# M206X.net
KiCad netlist of a schematic drawn in EAGLE
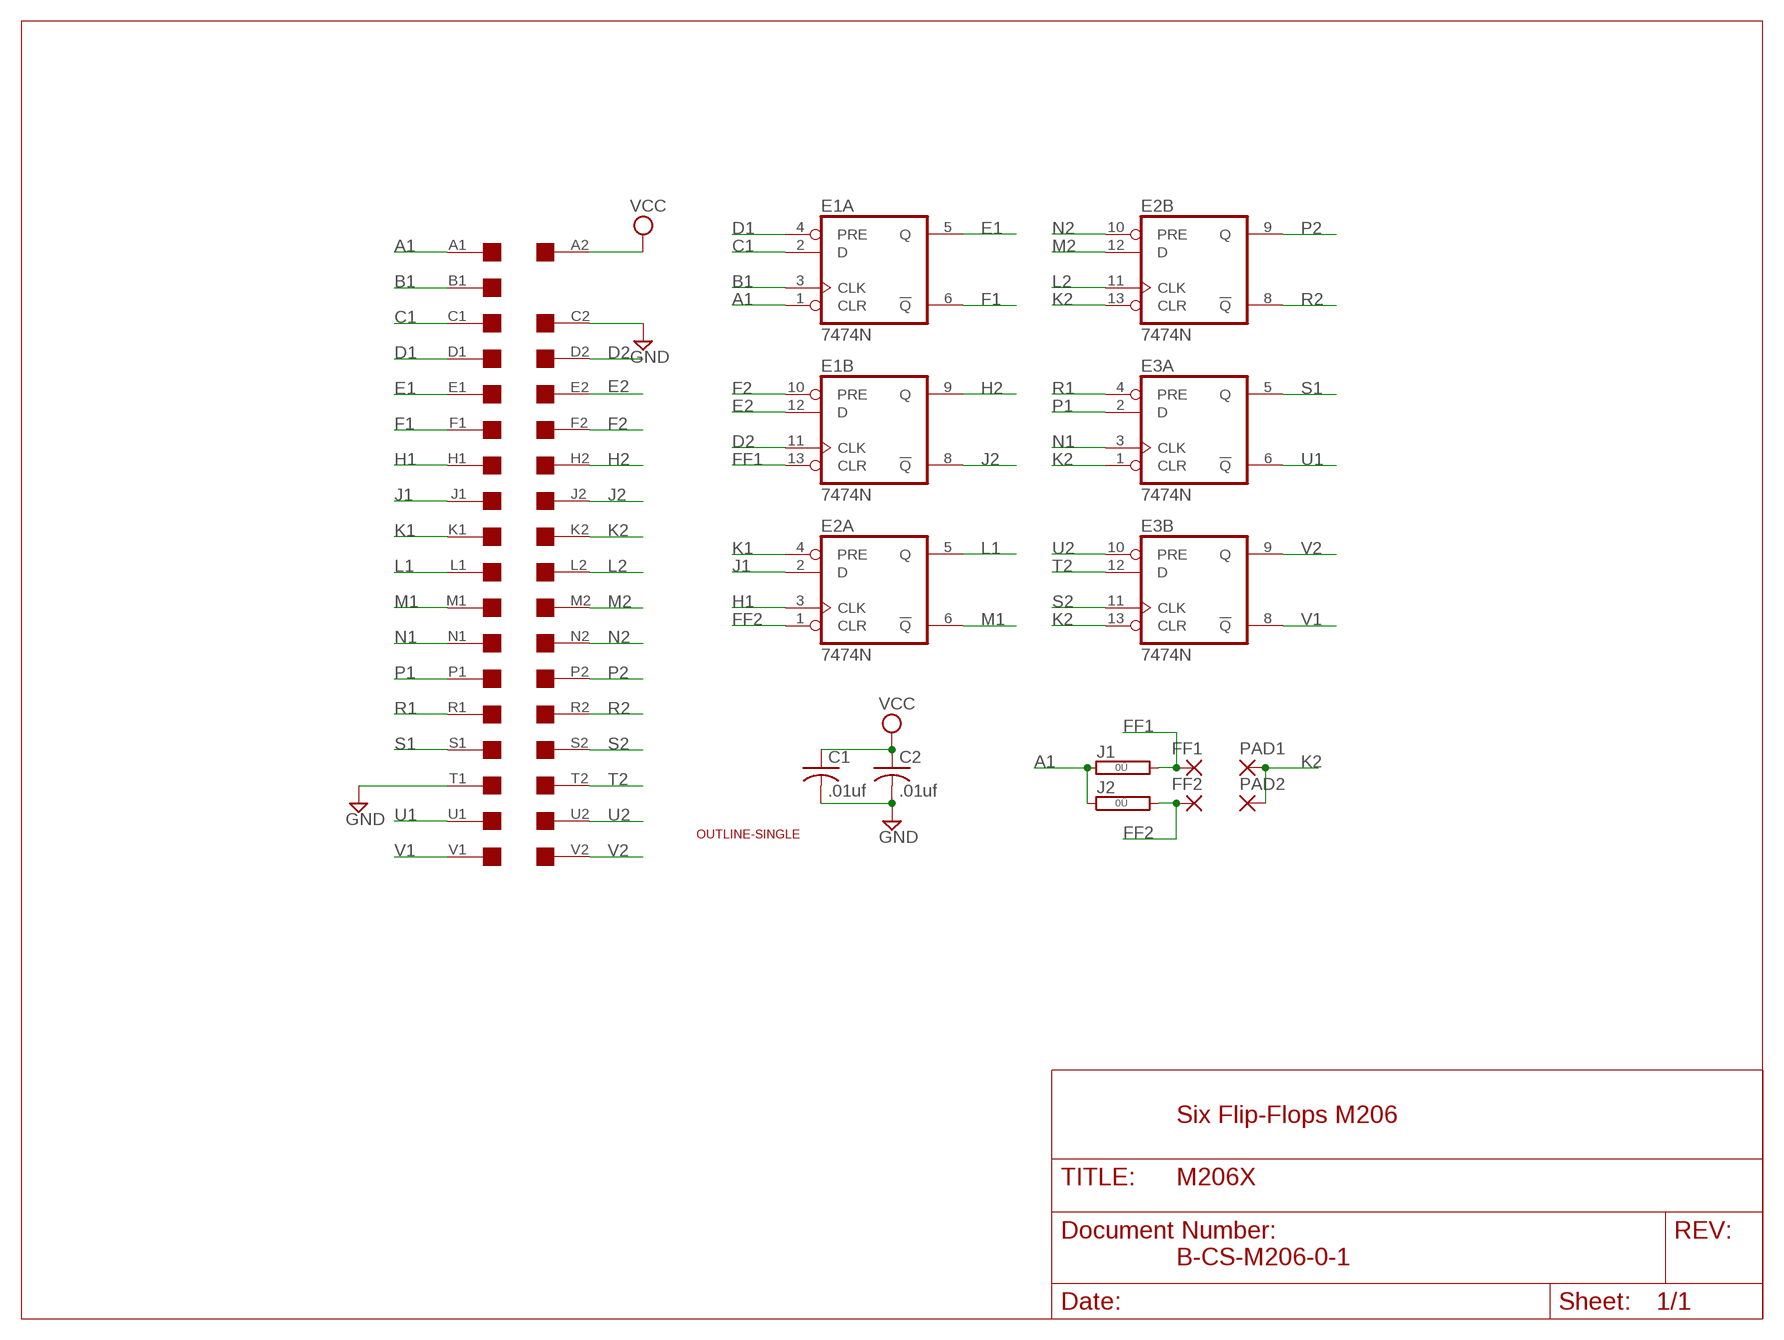
[diagram p0: schematic, sheet 1]

(export (version "E")
  (design (tool "Eeschema 10.0.6"))
  (components
    (comp (ref "C1")
      (value ".01uf")
      (footprint "eagle-import:C050-025X075")
      (libsource (lib "eagle-import") (part "C-US050-025X075"))
    )
    (comp (ref "C2")
      (value ".01uf")
      (footprint "eagle-import:C050-025X075")
      (libsource (lib "eagle-import") (part "C-US050-025X075"))
    )
    (comp (ref "E1")
      (value "7474N")
      (footprint "eagle-import:DIL14")
      (libsource (lib "eagle-import") (part "7474NS"))
    )
    (comp (ref "E2")
      (value "7474N")
      (footprint "eagle-import:DIL14")
      (libsource (lib "eagle-import") (part "7474NS"))
    )
    (comp (ref "E3")
      (value "7474N")
      (footprint "eagle-import:DIL14")
      (libsource (lib "eagle-import") (part "7474NS"))
    )
    (comp (ref "FF1")
      (value "1,6/0,8")
      (footprint "eagle-import:1,6_0,8")
      (libsource (lib "eagle-import") (part "1,6/0,8"))
    )
    (comp (ref "FF2")
      (value "1,6/0,8")
      (footprint "eagle-import:1,6_0,8")
      (libsource (lib "eagle-import") (part "1,6/0,8"))
    )
    (comp (ref "J1")
      (value "0R")
      (footprint "eagle-import:0R_10")
      (libsource (lib "eagle-import") (part "0R"))
    )
    (comp (ref "J2")
      (value "0R")
      (footprint "eagle-import:0R_10")
      (libsource (lib "eagle-import") (part "0R"))
    )
    (comp (ref "PAD1")
      (value "1,6/0,8")
      (footprint "eagle-import:1,6_0,8")
      (libsource (lib "eagle-import") (part "1,6/0,8"))
    )
    (comp (ref "PAD2")
      (value "1,6/0,8")
      (footprint "eagle-import:1,6_0,8")
      (libsource (lib "eagle-import") (part "1,6/0,8"))
    )
    (comp (ref "U$1")
      (value "OUTLINE-SINGLE")
      (footprint "eagle-import:SINGLE")
      (libsource (lib "eagle-import") (part "OUTLINE-SINGLE"))
    )
    (comp (ref "U$4")
      (value "SINGLE")
      (footprint "eagle-import:EDGE-CON2")
      (libsource (lib "eagle-import") (part "SINGLE"))
    )
  )
  (nets
    (net (code "1") (name "/A1") (class "Default")
      (node (ref "E1") (pin "1") (pinfunction "CLR_1") (pintype "input"))
      (node (ref "J1") (pin "1") (pinfunction "1_1") (pintype "passive"))
      (node (ref "J2") (pin "1") (pinfunction "1_1") (pintype "passive"))
      (node (ref "U$4") (pin "A1") (pinfunction "1_A1") (pintype "bidirectional"))
    )
    (net (code "2") (name "/B1") (class "Default")
      (node (ref "E1") (pin "3") (pinfunction "CLK_3") (pintype "input"))
      (node (ref "U$4") (pin "B1") (pinfunction "1_B1") (pintype "bidirectional"))
    )
    (net (code "3") (name "/C1") (class "Default")
      (node (ref "E1") (pin "2") (pinfunction "D_2") (pintype "input"))
      (node (ref "U$4") (pin "C1") (pinfunction "1_C1") (pintype "bidirectional"))
    )
    (net (code "4") (name "/D1") (class "Default")
      (node (ref "E1") (pin "4") (pinfunction "PRE_4") (pintype "input"))
      (node (ref "U$4") (pin "D1") (pinfunction "1_D1") (pintype "bidirectional"))
    )
    (net (code "5") (name "/D2") (class "Default")
      (node (ref "E1") (pin "11") (pinfunction "CLK_11") (pintype "input"))
      (node (ref "U$4") (pin "D2") (pinfunction "1_D2") (pintype "bidirectional"))
    )
    (net (code "6") (name "/E1") (class "Default")
      (node (ref "E1") (pin "5") (pinfunction "Q_5") (pintype "output"))
      (node (ref "U$4") (pin "E1") (pinfunction "1_E1") (pintype "bidirectional"))
    )
    (net (code "7") (name "/E2") (class "Default")
      (node (ref "E1") (pin "12") (pinfunction "D_12") (pintype "input"))
      (node (ref "U$4") (pin "E2") (pinfunction "1_E2") (pintype "bidirectional"))
    )
    (net (code "8") (name "/F1") (class "Default")
      (node (ref "E1") (pin "6") (pinfunction "~{Q}_6") (pintype "output"))
      (node (ref "U$4") (pin "F1") (pinfunction "1_F1") (pintype "bidirectional"))
    )
    (net (code "9") (name "/F2") (class "Default")
      (node (ref "E1") (pin "10") (pinfunction "PRE_10") (pintype "input"))
      (node (ref "U$4") (pin "F2") (pinfunction "1_F2") (pintype "bidirectional"))
    )
    (net (code "10") (name "/FF1") (class "Default")
      (node (ref "E1") (pin "13") (pinfunction "CLR_13") (pintype "input"))
      (node (ref "FF1") (pin "1") (pinfunction "P_1") (pintype "passive"))
      (node (ref "J1") (pin "2") (pinfunction "2_2") (pintype "passive"))
    )
    (net (code "11") (name "/FF2") (class "Default")
      (node (ref "E2") (pin "1") (pinfunction "CLR_1") (pintype "input"))
      (node (ref "FF2") (pin "1") (pinfunction "P_1") (pintype "passive"))
      (node (ref "J2") (pin "2") (pinfunction "2_2") (pintype "passive"))
    )
    (net (code "12") (name "/H1") (class "Default")
      (node (ref "E2") (pin "3") (pinfunction "CLK_3") (pintype "input"))
      (node (ref "U$4") (pin "H1") (pinfunction "1_H1") (pintype "bidirectional"))
    )
    (net (code "13") (name "/H2") (class "Default")
      (node (ref "E1") (pin "9") (pinfunction "Q_9") (pintype "output"))
      (node (ref "U$4") (pin "H2") (pinfunction "1_H2") (pintype "bidirectional"))
    )
    (net (code "14") (name "/J1") (class "Default")
      (node (ref "E2") (pin "2") (pinfunction "D_2") (pintype "input"))
      (node (ref "U$4") (pin "J1") (pinfunction "1_J1") (pintype "bidirectional"))
    )
    (net (code "15") (name "/J2") (class "Default")
      (node (ref "E1") (pin "8") (pinfunction "~{Q}_8") (pintype "output"))
      (node (ref "U$4") (pin "J2") (pinfunction "1_J2") (pintype "bidirectional"))
    )
    (net (code "16") (name "/K1") (class "Default")
      (node (ref "E2") (pin "4") (pinfunction "PRE_4") (pintype "input"))
      (node (ref "U$4") (pin "K1") (pinfunction "1_K1") (pintype "bidirectional"))
    )
    (net (code "17") (name "/K2") (class "Default")
      (node (ref "E2") (pin "13") (pinfunction "CLR_13") (pintype "input"))
      (node (ref "E3") (pin "1") (pinfunction "CLR_1") (pintype "input"))
      (node (ref "E3") (pin "13") (pinfunction "CLR_13") (pintype "input"))
      (node (ref "PAD1") (pin "1") (pinfunction "P_1") (pintype "passive"))
      (node (ref "PAD2") (pin "1") (pinfunction "P_1") (pintype "passive"))
      (node (ref "U$4") (pin "K2") (pinfunction "1_K2") (pintype "bidirectional"))
    )
    (net (code "18") (name "/L1") (class "Default")
      (node (ref "E2") (pin "5") (pinfunction "Q_5") (pintype "output"))
      (node (ref "U$4") (pin "L1") (pinfunction "1_L1") (pintype "bidirectional"))
    )
    (net (code "19") (name "/L2") (class "Default")
      (node (ref "E2") (pin "11") (pinfunction "CLK_11") (pintype "input"))
      (node (ref "U$4") (pin "L2") (pinfunction "1_L2") (pintype "bidirectional"))
    )
    (net (code "20") (name "/M1") (class "Default")
      (node (ref "E2") (pin "6") (pinfunction "~{Q}_6") (pintype "output"))
      (node (ref "U$4") (pin "M1") (pinfunction "1_M1") (pintype "bidirectional"))
    )
    (net (code "21") (name "/M2") (class "Default")
      (node (ref "E2") (pin "12") (pinfunction "D_12") (pintype "input"))
      (node (ref "U$4") (pin "M2") (pinfunction "1_M2") (pintype "bidirectional"))
    )
    (net (code "22") (name "/N1") (class "Default")
      (node (ref "E3") (pin "3") (pinfunction "CLK_3") (pintype "input"))
      (node (ref "U$4") (pin "N1") (pinfunction "1_N1") (pintype "bidirectional"))
    )
    (net (code "23") (name "/N2") (class "Default")
      (node (ref "E2") (pin "10") (pinfunction "PRE_10") (pintype "input"))
      (node (ref "U$4") (pin "N2") (pinfunction "1_N2") (pintype "bidirectional"))
    )
    (net (code "24") (name "/P1") (class "Default")
      (node (ref "E3") (pin "2") (pinfunction "D_2") (pintype "input"))
      (node (ref "U$4") (pin "P1") (pinfunction "1_P1") (pintype "bidirectional"))
    )
    (net (code "25") (name "/P2") (class "Default")
      (node (ref "E2") (pin "9") (pinfunction "Q_9") (pintype "output"))
      (node (ref "U$4") (pin "P2") (pinfunction "1_P2") (pintype "bidirectional"))
    )
    (net (code "26") (name "/R1") (class "Default")
      (node (ref "E3") (pin "4") (pinfunction "PRE_4") (pintype "input"))
      (node (ref "U$4") (pin "R1") (pinfunction "1_R1") (pintype "bidirectional"))
    )
    (net (code "27") (name "/R2") (class "Default")
      (node (ref "E2") (pin "8") (pinfunction "~{Q}_8") (pintype "output"))
      (node (ref "U$4") (pin "R2") (pinfunction "1_R2") (pintype "bidirectional"))
    )
    (net (code "28") (name "/S1") (class "Default")
      (node (ref "E3") (pin "5") (pinfunction "Q_5") (pintype "output"))
      (node (ref "U$4") (pin "S1") (pinfunction "1_S1") (pintype "bidirectional"))
    )
    (net (code "29") (name "/S2") (class "Default")
      (node (ref "E3") (pin "11") (pinfunction "CLK_11") (pintype "input"))
      (node (ref "U$4") (pin "S2") (pinfunction "1_S2") (pintype "bidirectional"))
    )
    (net (code "30") (name "/T2") (class "Default")
      (node (ref "E3") (pin "12") (pinfunction "D_12") (pintype "input"))
      (node (ref "U$4") (pin "T2") (pinfunction "1_T2") (pintype "bidirectional"))
    )
    (net (code "31") (name "/U1") (class "Default")
      (node (ref "E3") (pin "6") (pinfunction "~{Q}_6") (pintype "output"))
      (node (ref "U$4") (pin "U1") (pinfunction "1_U1") (pintype "bidirectional"))
    )
    (net (code "32") (name "/U2") (class "Default")
      (node (ref "E3") (pin "10") (pinfunction "PRE_10") (pintype "input"))
      (node (ref "U$4") (pin "U2") (pinfunction "1_U2") (pintype "bidirectional"))
    )
    (net (code "33") (name "/V1") (class "Default")
      (node (ref "E3") (pin "8") (pinfunction "~{Q}_8") (pintype "output"))
      (node (ref "U$4") (pin "V1") (pinfunction "1_V1") (pintype "bidirectional"))
    )
    (net (code "34") (name "/V2") (class "Default")
      (node (ref "E3") (pin "9") (pinfunction "Q_9") (pintype "output"))
      (node (ref "U$4") (pin "V2") (pinfunction "1_V2") (pintype "bidirectional"))
    )
    (net (code "35") (name "GND") (class "Default")
      (node (ref "C1") (pin "2") (pinfunction "2_2") (pintype "passive"))
      (node (ref "C2") (pin "2") (pinfunction "2_2") (pintype "passive"))
      (node (ref "U$4") (pin "C2") (pinfunction "1_C2") (pintype "bidirectional"))
      (node (ref "U$4") (pin "T1") (pinfunction "1_T1") (pintype "bidirectional"))
    )
    (net (code "36") (name "VCC") (class "Default")
      (node (ref "C1") (pin "1") (pinfunction "1_1") (pintype "passive"))
      (node (ref "C2") (pin "1") (pinfunction "1_1") (pintype "passive"))
      (node (ref "U$4") (pin "A2") (pinfunction "1_A2") (pintype "bidirectional"))
    )
  )
)
